# backlight_control.net
KiCad netlist of a schematic drawn in Altium Designer
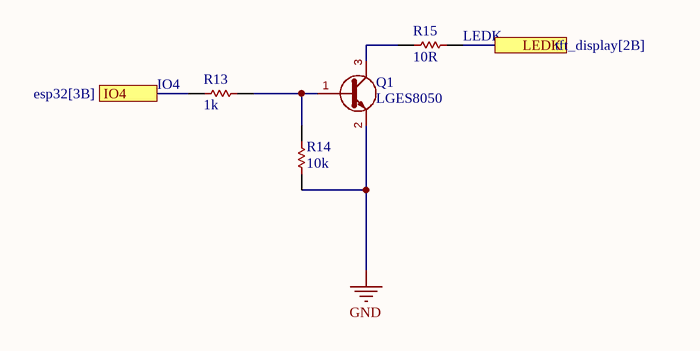
[diagram p0: backlight_control.SchDoc]

(export (version "E")
  (design (tool "Eeschema 10.0.6"))
  (components
    (comp (ref "Q1")
      (value "LGES8050")
      (footprint "FP-SS8050-G-IPC_A")
      (libsource (lib "Thermal_Camera") (part "LGES8050"))
    )
    (comp (ref "R13")
      (value "1k")
      (footprint "RESC2013X70X40NL20T20")
      (description "Chip Resistor, 1 KOhm, +/- 1%, 125 mW, -55 to 155 degC, 0805 (2012 Metric), RoHS, Tape and Reel")
      (fields (field (name "TOLERANCE") "1%") (field (name "MANUFACTURER") "Yageo"))
      (libsource (lib "Thermal_Camera") (part "CMP-2100-03671-1"))
    )
    (comp (ref "R14")
      (value "10k")
      (footprint "RESC2013X70X40NL20T20")
      (description "Chip Resistor, 1 KOhm, +/- 1%, 125 mW, -55 to 155 degC, 0805 (2012 Metric), RoHS, Tape and Reel")
      (fields (field (name "TOLERANCE") "1%") (field (name "MANUFACTURER") "Yageo"))
      (libsource (lib "Thermal_Camera") (part "CMP-2100-03671-1"))
    )
    (comp (ref "R15")
      (value "10R")
      (footprint "RESC2013X70X40NL20T20")
      (description "Chip Resistor, 1 KOhm, +/- 1%, 125 mW, -55 to 155 degC, 0805 (2012 Metric), RoHS, Tape and Reel")
      (fields (field (name "TOLERANCE") "1%") (field (name "MANUFACTURER") "Yageo"))
      (libsource (lib "Thermal_Camera") (part "CMP-2100-03671-1"))
    )
  )
  (nets
    (net (code "1") (name "/IO4") (class "Default")
      (node (ref "R13") (pin "2") (pinfunction "2_2") (pintype "passive"))
    )
    (net (code "2") (name "/LEDK") (class "Default")
      (node (ref "R15") (pin "1") (pinfunction "1_1") (pintype "passive"))
    )
    (net (code "3") (name "GND") (class "Default")
      (node (ref "Q1") (pin "2") (pinfunction "B_2") (pintype "passive"))
      (node (ref "R14") (pin "1") (pinfunction "1_1") (pintype "passive"))
    )
    (net (code "4") (name "Net-(Q1-C)") (class "Default")
      (node (ref "Q1") (pin "3") (pinfunction "C_3") (pintype "passive"))
      (node (ref "R15") (pin "2") (pinfunction "2_2") (pintype "passive"))
    )
    (net (code "5") (name "Net-(Q1-E)") (class "Default")
      (node (ref "Q1") (pin "1") (pinfunction "E_1") (pintype "passive"))
      (node (ref "R13") (pin "1") (pinfunction "1_1") (pintype "passive"))
      (node (ref "R14") (pin "2") (pinfunction "2_2") (pintype "passive"))
    )
  )
)
